# pt3MX.net
KiCad netlist of a schematic drawn in EAGLE
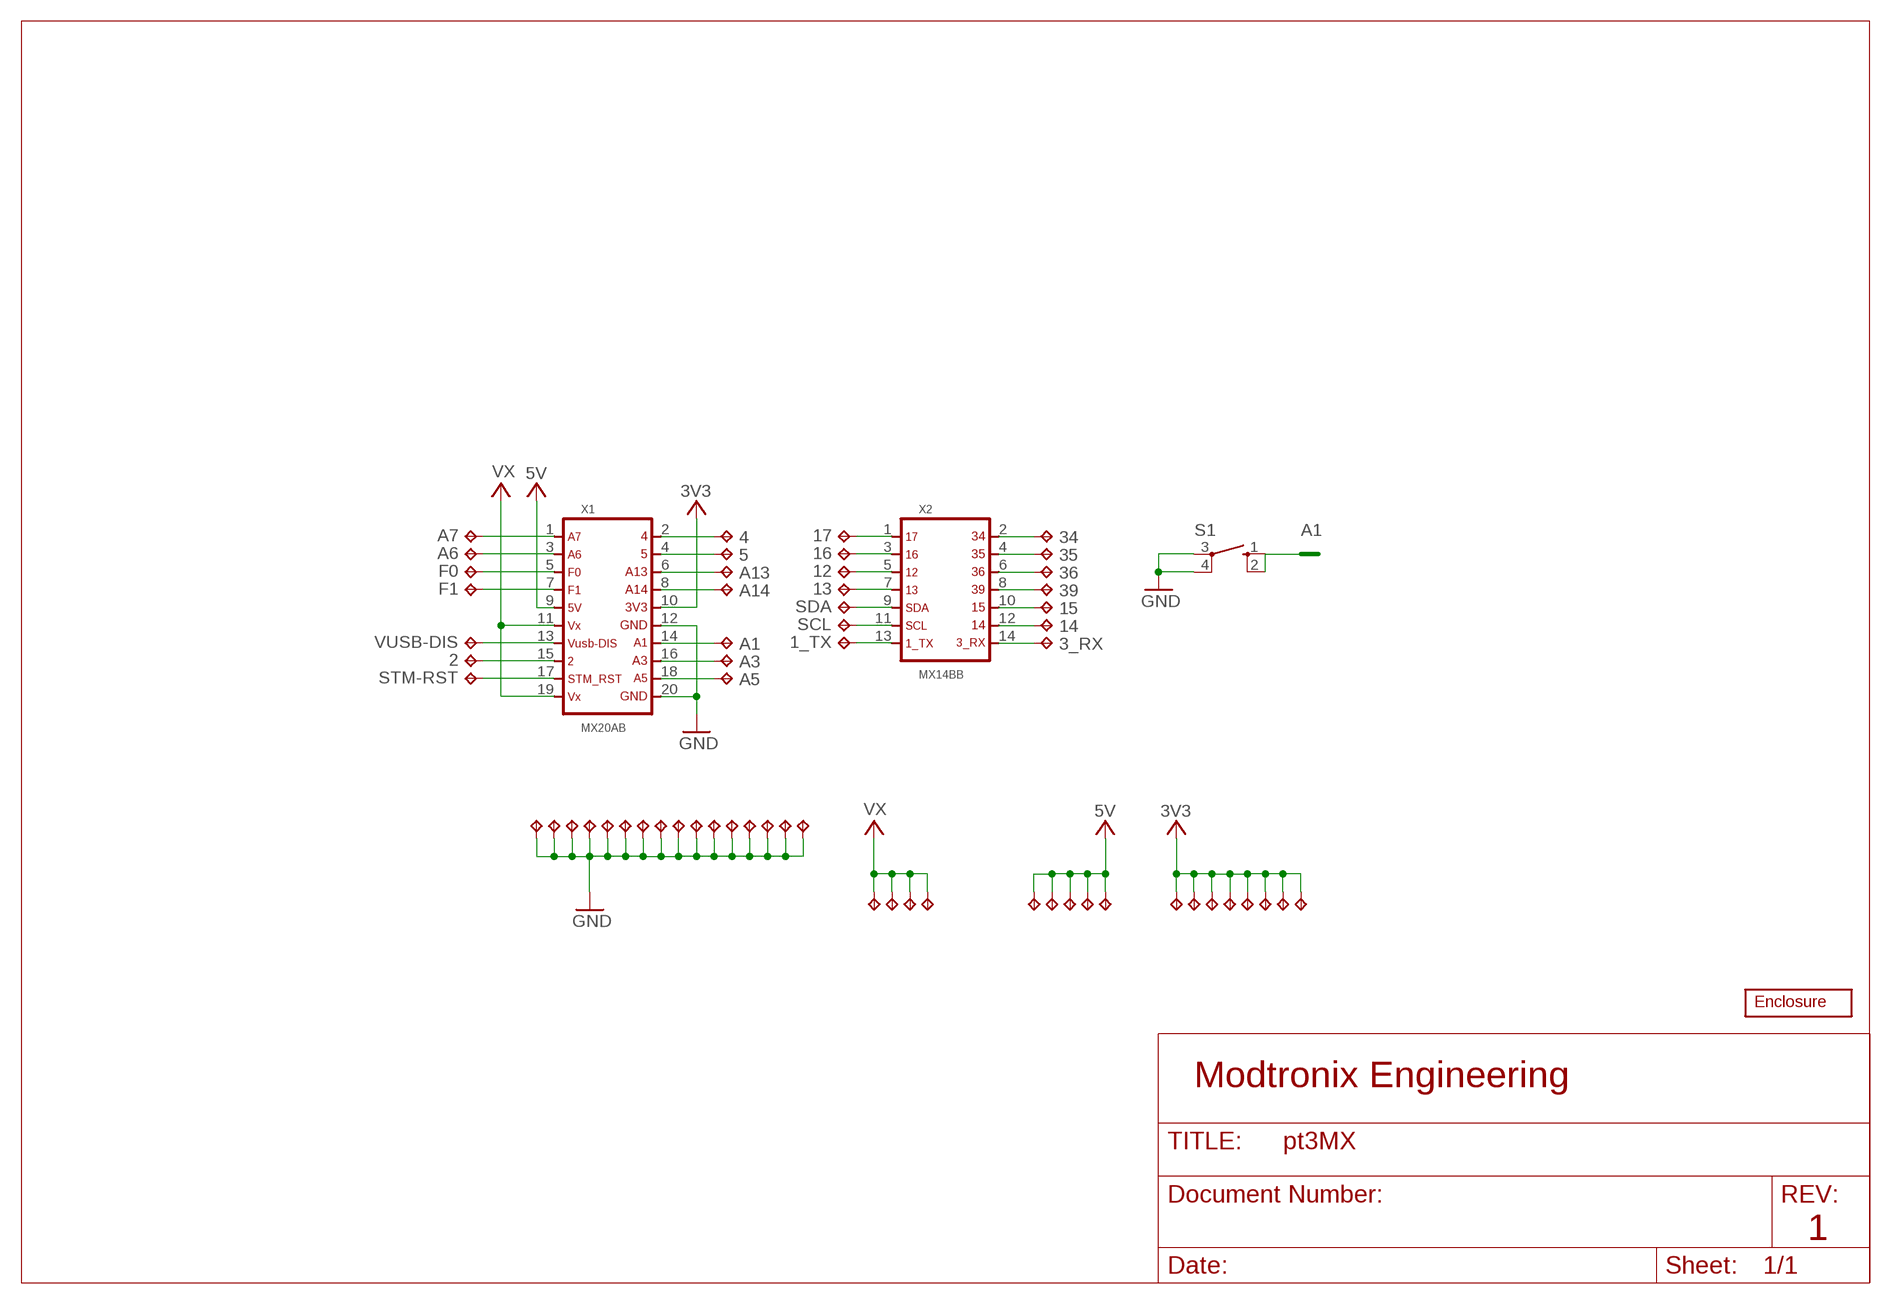
[diagram p0: schematic, sheet 1]

(export (version "E")
  (design (tool "Eeschema 10.0.6"))
  (components
    (comp (ref "1_TX")
      (value "TPD10B")
      (footprint "eagle-import:TP-10B")
      (libsource (lib "eagle-import") (part "TPD10B"))
    )
    (comp (ref "2")
      (value "TPD10B")
      (footprint "eagle-import:TP-10B")
      (libsource (lib "eagle-import") (part "TPD10B"))
    )
    (comp (ref "3_RX")
      (value "TPD10B")
      (footprint "eagle-import:TP-10B")
      (libsource (lib "eagle-import") (part "TPD10B"))
    )
    (comp (ref "4")
      (value "TPD10C")
      (footprint "eagle-import:TP-10C")
      (libsource (lib "eagle-import") (part "TPD10C"))
    )
    (comp (ref "5")
      (value "TPD10B")
      (footprint "eagle-import:TP-10B")
      (libsource (lib "eagle-import") (part "TPD10B"))
    )
    (comp (ref "12")
      (value "TPD10B")
      (footprint "eagle-import:TP-10B")
      (libsource (lib "eagle-import") (part "TPD10B"))
    )
    (comp (ref "13")
      (value "TPD10B")
      (footprint "eagle-import:TP-10B")
      (libsource (lib "eagle-import") (part "TPD10B"))
    )
    (comp (ref "14")
      (value "TPD10B")
      (footprint "eagle-import:TP-10B")
      (libsource (lib "eagle-import") (part "TPD10B"))
    )
    (comp (ref "15")
      (value "TPD10C")
      (footprint "eagle-import:TP-10C")
      (libsource (lib "eagle-import") (part "TPD10C"))
    )
    (comp (ref "16")
      (value "TPD10B")
      (footprint "eagle-import:TP-10B")
      (libsource (lib "eagle-import") (part "TPD10B"))
    )
    (comp (ref "17")
      (value "TPD10B")
      (footprint "eagle-import:TP-10B")
      (libsource (lib "eagle-import") (part "TPD10B"))
    )
    (comp (ref "34")
      (value "TPD10C")
      (footprint "eagle-import:TP-10C")
      (libsource (lib "eagle-import") (part "TPD10C"))
    )
    (comp (ref "35")
      (value "TPD10C")
      (footprint "eagle-import:TP-10C")
      (libsource (lib "eagle-import") (part "TPD10C"))
    )
    (comp (ref "36")
      (value "TPD10B")
      (footprint "eagle-import:TP-10B")
      (libsource (lib "eagle-import") (part "TPD10B"))
    )
    (comp (ref "39")
      (value "TPD10B")
      (footprint "eagle-import:TP-10B")
      (libsource (lib "eagle-import") (part "TPD10B"))
    )
    (comp (ref "A1")
      (value "TPD10-D200")
      (footprint "eagle-import:TP-10-D200")
      (libsource (lib "eagle-import") (part "TPD10-D200"))
    )
    (comp (ref "A3")
      (value "TPD10-D200")
      (footprint "eagle-import:TP-10-D200")
      (libsource (lib "eagle-import") (part "TPD10-D200"))
    )
    (comp (ref "A5")
      (value "TPD10B")
      (footprint "eagle-import:TP-10B")
      (libsource (lib "eagle-import") (part "TPD10B"))
    )
    (comp (ref "A6")
      (value "TPD10B")
      (footprint "eagle-import:TP-10B")
      (libsource (lib "eagle-import") (part "TPD10B"))
    )
    (comp (ref "A7")
      (value "TPD10B")
      (footprint "eagle-import:TP-10B")
      (libsource (lib "eagle-import") (part "TPD10B"))
    )
    (comp (ref "A13")
      (value "TPD10B")
      (footprint "eagle-import:TP-10B")
      (libsource (lib "eagle-import") (part "TPD10B"))
    )
    (comp (ref "A14")
      (value "TPD10C")
      (footprint "eagle-import:TP-10C")
      (libsource (lib "eagle-import") (part "TPD10C"))
    )
    (comp (ref "F0")
      (value "TPD10C")
      (footprint "eagle-import:TP-10C")
      (libsource (lib "eagle-import") (part "TPD10C"))
    )
    (comp (ref "F1")
      (value "TPD10-D200")
      (footprint "eagle-import:TP-10-D200")
      (libsource (lib "eagle-import") (part "TPD10-D200"))
    )
    (comp (ref "S1")
      (value "SWITCH-MICRO")
      (footprint "eagle-import:SW-TACTILE-4P-TH")
      (libsource (lib "eagle-import") (part "SWITCH-MICRO"))
    )
    (comp (ref "SCL")
      (value "TPD10B")
      (footprint "eagle-import:TP-10B")
      (libsource (lib "eagle-import") (part "TPD10B"))
    )
    (comp (ref "SDA")
      (value "TPD10C")
      (footprint "eagle-import:TP-10C")
      (libsource (lib "eagle-import") (part "TPD10C"))
    )
    (comp (ref "STM-RST")
      (value "TPD10B")
      (footprint "eagle-import:TP-10B")
      (libsource (lib "eagle-import") (part "TPD10B"))
    )
    (comp (ref "U$1")
      (value "ENC_2015SMX-AND-EC-B")
      (footprint "eagle-import:ENC_2015S_3H_MX-AND-EC_DIM-MSR_B")
      (libsource (lib "eagle-import") (part "ENC_2015SMX-AND-EC-B"))
    )
    (comp (ref "U$2")
      (value "TPD10-D205")
      (footprint "eagle-import:TP-10-D205")
      (libsource (lib "eagle-import") (part "TPD10-D205"))
    )
    (comp (ref "U$5")
      (value "TPD10D")
      (footprint "eagle-import:TP-10D")
      (libsource (lib "eagle-import") (part "TPD10D"))
    )
    (comp (ref "U$6")
      (value "TPD10-D205")
      (footprint "eagle-import:TP-10-D205")
      (libsource (lib "eagle-import") (part "TPD10-D205"))
    )
    (comp (ref "U$7")
      (value "TPD10-D205")
      (footprint "eagle-import:TP-10-D205")
      (libsource (lib "eagle-import") (part "TPD10-D205"))
    )
    (comp (ref "U$8")
      (value "TPD10-D205")
      (footprint "eagle-import:TP-10-D205")
      (libsource (lib "eagle-import") (part "TPD10-D205"))
    )
    (comp (ref "U$10")
      (value "TPD10D")
      (footprint "eagle-import:TP-10D")
      (libsource (lib "eagle-import") (part "TPD10D"))
    )
    (comp (ref "U$11")
      (value "TPD10C")
      (footprint "eagle-import:TP-10C")
      (libsource (lib "eagle-import") (part "TPD10C"))
    )
    (comp (ref "U$12")
      (value "TPD10-D205")
      (footprint "eagle-import:TP-10-D205")
      (libsource (lib "eagle-import") (part "TPD10-D205"))
    )
    (comp (ref "U$13")
      (value "TPD10C")
      (footprint "eagle-import:TP-10C")
      (libsource (lib "eagle-import") (part "TPD10C"))
    )
    (comp (ref "U$14")
      (value "TPD10")
      (footprint "eagle-import:TP-10")
      (libsource (lib "eagle-import") (part "TPD10"))
    )
    (comp (ref "U$17")
      (value "TPD10-D205")
      (footprint "eagle-import:TP-10-D205")
      (libsource (lib "eagle-import") (part "TPD10-D205"))
    )
    (comp (ref "U$22")
      (value "TPD10-D205")
      (footprint "eagle-import:TP-10-D205")
      (libsource (lib "eagle-import") (part "TPD10-D205"))
    )
    (comp (ref "U$23")
      (value "TPD10C")
      (footprint "eagle-import:TP-10C")
      (libsource (lib "eagle-import") (part "TPD10C"))
    )
    (comp (ref "U$24")
      (value "TPD10C")
      (footprint "eagle-import:TP-10C")
      (libsource (lib "eagle-import") (part "TPD10C"))
    )
    (comp (ref "U$25")
      (value "TPD10C")
      (footprint "eagle-import:TP-10C")
      (libsource (lib "eagle-import") (part "TPD10C"))
    )
    (comp (ref "U$26")
      (value "TPD10C")
      (footprint "eagle-import:TP-10C")
      (libsource (lib "eagle-import") (part "TPD10C"))
    )
    (comp (ref "U$27")
      (value "TPD10C")
      (footprint "eagle-import:TP-10C")
      (libsource (lib "eagle-import") (part "TPD10C"))
    )
    (comp (ref "U$28")
      (value "TPD10C")
      (footprint "eagle-import:TP-10C")
      (libsource (lib "eagle-import") (part "TPD10C"))
    )
    (comp (ref "U$29")
      (value "TPD10C")
      (footprint "eagle-import:TP-10C")
      (libsource (lib "eagle-import") (part "TPD10C"))
    )
    (comp (ref "U$30")
      (value "TPD10C")
      (footprint "eagle-import:TP-10C")
      (libsource (lib "eagle-import") (part "TPD10C"))
    )
    (comp (ref "U$31")
      (value "TPD10C")
      (footprint "eagle-import:TP-10C")
      (libsource (lib "eagle-import") (part "TPD10C"))
    )
    (comp (ref "U$32")
      (value "TPD10C")
      (footprint "eagle-import:TP-10C")
      (libsource (lib "eagle-import") (part "TPD10C"))
    )
    (comp (ref "U$33")
      (value "TPD10B")
      (footprint "eagle-import:TP-10B")
      (libsource (lib "eagle-import") (part "TPD10B"))
    )
    (comp (ref "U$34")
      (value "TPD10C")
      (footprint "eagle-import:TP-10C")
      (libsource (lib "eagle-import") (part "TPD10C"))
    )
    (comp (ref "U$35")
      (value "TPD10C")
      (footprint "eagle-import:TP-10C")
      (libsource (lib "eagle-import") (part "TPD10C"))
    )
    (comp (ref "U$36")
      (value "TPD10C")
      (footprint "eagle-import:TP-10C")
      (libsource (lib "eagle-import") (part "TPD10C"))
    )
    (comp (ref "U$53")
      (value "TPD10-D205")
      (footprint "eagle-import:TP-10-D205")
      (libsource (lib "eagle-import") (part "TPD10-D205"))
    )
    (comp (ref "U$58")
      (value "TPD10C")
      (footprint "eagle-import:TP-10C")
      (libsource (lib "eagle-import") (part "TPD10C"))
    )
    (comp (ref "U$60")
      (value "TPD10-D205")
      (footprint "eagle-import:TP-10-D205")
      (libsource (lib "eagle-import") (part "TPD10-D205"))
    )
    (comp (ref "U$85")
      (value "TPD10-D205")
      (footprint "eagle-import:TP-10-D205")
      (libsource (lib "eagle-import") (part "TPD10-D205"))
    )
    (comp (ref "U$86")
      (value "TPD10-D205")
      (footprint "eagle-import:TP-10-D205")
      (libsource (lib "eagle-import") (part "TPD10-D205"))
    )
    (comp (ref "U$87")
      (value "TPD10-D205")
      (footprint "eagle-import:TP-10-D205")
      (libsource (lib "eagle-import") (part "TPD10-D205"))
    )
    (comp (ref "U$90")
      (value "TPD10-D205")
      (footprint "eagle-import:TP-10-D205")
      (libsource (lib "eagle-import") (part "TPD10-D205"))
    )
    (comp (ref "VUSB-DIS")
      (value "TPD10B")
      (footprint "eagle-import:TP-10B")
      (libsource (lib "eagle-import") (part "TPD10B"))
    )
    (comp (ref "X1")
      (value "MX20AB")
      (footprint "eagle-import:MA10-2-NONUM")
      (libsource (lib "eagle-import") (part "MX20AB"))
    )
    (comp (ref "X2")
      (value "MX14BB")
      (footprint "eagle-import:MA07-2-NONUM")
      (libsource (lib "eagle-import") (part "MX14BB"))
    )
  )
  (nets
    (net (code "1") (name "/A1") (class "Default")
      (node (ref "A1") (pin "1") (pinfunction "TP_1") (pintype "input"))
      (node (ref "S1") (pin "1") (pinfunction "S_1") (pintype "passive"))
      (node (ref "S1") (pin "2") (pinfunction "S1_2") (pintype "passive"))
      (node (ref "X1") (pin "14") (pinfunction "14_14") (pintype "passive"))
    )
    (net (code "2") (name "3V3") (class "Default")
      (node (ref "U$14") (pin "1") (pinfunction "TP_1") (pintype "input"))
      (node (ref "U$25") (pin "1") (pinfunction "TP_1") (pintype "input"))
      (node (ref "U$26") (pin "1") (pinfunction "TP_1") (pintype "input"))
      (node (ref "U$31") (pin "1") (pinfunction "TP_1") (pintype "input"))
      (node (ref "U$32") (pin "1") (pinfunction "TP_1") (pintype "input"))
      (node (ref "U$53") (pin "1") (pinfunction "TP_1") (pintype "input"))
      (node (ref "U$85") (pin "1") (pinfunction "TP_1") (pintype "input"))
      (node (ref "U$86") (pin "1") (pinfunction "TP_1") (pintype "input"))
      (node (ref "X1") (pin "10") (pinfunction "10_10") (pintype "passive"))
    )
    (net (code "3") (name "5V") (class "Default")
      (node (ref "U$12") (pin "1") (pinfunction "TP_1") (pintype "input"))
      (node (ref "U$13") (pin "1") (pinfunction "TP_1") (pintype "input"))
      (node (ref "U$23") (pin "1") (pinfunction "TP_1") (pintype "input"))
      (node (ref "U$24") (pin "1") (pinfunction "TP_1") (pintype "input"))
      (node (ref "U$87") (pin "1") (pinfunction "TP_1") (pintype "input"))
      (node (ref "X1") (pin "9") (pinfunction "9_9") (pintype "passive"))
    )
    (net (code "4") (name "GND") (class "Default")
      (node (ref "S1") (pin "3") (pinfunction "P_3") (pintype "passive"))
      (node (ref "S1") (pin "4") (pinfunction "P1_4") (pintype "passive"))
      (node (ref "U$10") (pin "1") (pinfunction "TP_1") (pintype "input"))
      (node (ref "U$11") (pin "1") (pinfunction "TP_1") (pintype "input"))
      (node (ref "U$17") (pin "1") (pinfunction "TP_1") (pintype "input"))
      (node (ref "U$22") (pin "1") (pinfunction "TP_1") (pintype "input"))
      (node (ref "U$27") (pin "1") (pinfunction "TP_1") (pintype "input"))
      (node (ref "U$28") (pin "1") (pinfunction "TP_1") (pintype "input"))
      (node (ref "U$29") (pin "1") (pinfunction "TP_1") (pintype "input"))
      (node (ref "U$30") (pin "1") (pinfunction "TP_1") (pintype "input"))
      (node (ref "U$34") (pin "1") (pinfunction "TP_1") (pintype "input"))
      (node (ref "U$35") (pin "1") (pinfunction "TP_1") (pintype "input"))
      (node (ref "U$36") (pin "1") (pinfunction "TP_1") (pintype "input"))
      (node (ref "U$5") (pin "1") (pinfunction "TP_1") (pintype "input"))
      (node (ref "U$6") (pin "1") (pinfunction "TP_1") (pintype "input"))
      (node (ref "U$60") (pin "1") (pinfunction "TP_1") (pintype "input"))
      (node (ref "U$7") (pin "1") (pinfunction "TP_1") (pintype "input"))
      (node (ref "U$8") (pin "1") (pinfunction "TP_1") (pintype "input"))
      (node (ref "X1") (pin "12") (pinfunction "12_12") (pintype "passive"))
      (node (ref "X1") (pin "20") (pinfunction "20_20") (pintype "passive"))
    )
    (net (code "5") (name "Net-(1_TX-TP)") (class "Default")
      (node (ref "1_TX") (pin "1") (pinfunction "TP_1") (pintype "input"))
      (node (ref "X2") (pin "13") (pinfunction "13_13") (pintype "passive"))
    )
    (net (code "6") (name "Net-(2-TP)") (class "Default")
      (node (ref "2") (pin "1") (pinfunction "TP_1") (pintype "input"))
      (node (ref "X1") (pin "15") (pinfunction "15_15") (pintype "passive"))
    )
    (net (code "7") (name "Net-(3_RX-TP)") (class "Default")
      (node (ref "3_RX") (pin "1") (pinfunction "TP_1") (pintype "input"))
      (node (ref "X2") (pin "14") (pinfunction "14_14") (pintype "passive"))
    )
    (net (code "8") (name "Net-(4-TP)") (class "Default")
      (node (ref "4") (pin "1") (pinfunction "TP_1") (pintype "input"))
      (node (ref "X1") (pin "2") (pinfunction "2_2") (pintype "passive"))
    )
    (net (code "9") (name "Net-(5-TP)") (class "Default")
      (node (ref "5") (pin "1") (pinfunction "TP_1") (pintype "input"))
      (node (ref "X1") (pin "4") (pinfunction "4_4") (pintype "passive"))
    )
    (net (code "10") (name "Net-(12-TP)") (class "Default")
      (node (ref "12") (pin "1") (pinfunction "TP_1") (pintype "input"))
      (node (ref "X2") (pin "5") (pinfunction "5_5") (pintype "passive"))
    )
    (net (code "11") (name "Net-(13-TP)") (class "Default")
      (node (ref "13") (pin "1") (pinfunction "TP_1") (pintype "input"))
      (node (ref "X2") (pin "7") (pinfunction "7_7") (pintype "passive"))
    )
    (net (code "12") (name "Net-(14-TP)") (class "Default")
      (node (ref "14") (pin "1") (pinfunction "TP_1") (pintype "input"))
      (node (ref "X2") (pin "12") (pinfunction "12_12") (pintype "passive"))
    )
    (net (code "13") (name "Net-(15-TP)") (class "Default")
      (node (ref "15") (pin "1") (pinfunction "TP_1") (pintype "input"))
      (node (ref "X2") (pin "10") (pinfunction "10_10") (pintype "passive"))
    )
    (net (code "14") (name "Net-(16-TP)") (class "Default")
      (node (ref "16") (pin "1") (pinfunction "TP_1") (pintype "input"))
      (node (ref "X2") (pin "3") (pinfunction "3_3") (pintype "passive"))
    )
    (net (code "15") (name "Net-(17-TP)") (class "Default")
      (node (ref "17") (pin "1") (pinfunction "TP_1") (pintype "input"))
      (node (ref "X2") (pin "1") (pinfunction "1_1") (pintype "passive"))
    )
    (net (code "16") (name "Net-(34-TP)") (class "Default")
      (node (ref "34") (pin "1") (pinfunction "TP_1") (pintype "input"))
      (node (ref "X2") (pin "2") (pinfunction "2_2") (pintype "passive"))
    )
    (net (code "17") (name "Net-(35-TP)") (class "Default")
      (node (ref "35") (pin "1") (pinfunction "TP_1") (pintype "input"))
      (node (ref "X2") (pin "4") (pinfunction "4_4") (pintype "passive"))
    )
    (net (code "18") (name "Net-(36-TP)") (class "Default")
      (node (ref "36") (pin "1") (pinfunction "TP_1") (pintype "input"))
      (node (ref "X2") (pin "6") (pinfunction "6_6") (pintype "passive"))
    )
    (net (code "19") (name "Net-(39-TP)") (class "Default")
      (node (ref "39") (pin "1") (pinfunction "TP_1") (pintype "input"))
      (node (ref "X2") (pin "8") (pinfunction "8_8") (pintype "passive"))
    )
    (net (code "20") (name "Net-(A3-TP)") (class "Default")
      (node (ref "A3") (pin "1") (pinfunction "TP_1") (pintype "input"))
      (node (ref "X1") (pin "16") (pinfunction "16_16") (pintype "passive"))
    )
    (net (code "21") (name "Net-(A5-TP)") (class "Default")
      (node (ref "A5") (pin "1") (pinfunction "TP_1") (pintype "input"))
      (node (ref "X1") (pin "18") (pinfunction "18_18") (pintype "passive"))
    )
    (net (code "22") (name "Net-(A6-TP)") (class "Default")
      (node (ref "A6") (pin "1") (pinfunction "TP_1") (pintype "input"))
      (node (ref "X1") (pin "3") (pinfunction "3_3") (pintype "passive"))
    )
    (net (code "23") (name "Net-(A7-TP)") (class "Default")
      (node (ref "A7") (pin "1") (pinfunction "TP_1") (pintype "input"))
      (node (ref "X1") (pin "1") (pinfunction "1_1") (pintype "passive"))
    )
    (net (code "24") (name "Net-(A13-TP)") (class "Default")
      (node (ref "A13") (pin "1") (pinfunction "TP_1") (pintype "input"))
      (node (ref "X1") (pin "6") (pinfunction "6_6") (pintype "passive"))
    )
    (net (code "25") (name "Net-(A14-TP)") (class "Default")
      (node (ref "A14") (pin "1") (pinfunction "TP_1") (pintype "input"))
      (node (ref "X1") (pin "8") (pinfunction "8_8") (pintype "passive"))
    )
    (net (code "26") (name "Net-(F0-TP)") (class "Default")
      (node (ref "F0") (pin "1") (pinfunction "TP_1") (pintype "input"))
      (node (ref "X1") (pin "5") (pinfunction "5_5") (pintype "passive"))
    )
    (net (code "27") (name "Net-(F1-TP)") (class "Default")
      (node (ref "F1") (pin "1") (pinfunction "TP_1") (pintype "input"))
      (node (ref "X1") (pin "7") (pinfunction "7_7") (pintype "passive"))
    )
    (net (code "28") (name "Net-(SCL-TP)") (class "Default")
      (node (ref "SCL") (pin "1") (pinfunction "TP_1") (pintype "input"))
      (node (ref "X2") (pin "11") (pinfunction "11_11") (pintype "passive"))
    )
    (net (code "29") (name "Net-(SDA-TP)") (class "Default")
      (node (ref "SDA") (pin "1") (pinfunction "TP_1") (pintype "input"))
      (node (ref "X2") (pin "9") (pinfunction "9_9") (pintype "passive"))
    )
    (net (code "30") (name "Net-(STM-RST-TP)") (class "Default")
      (node (ref "STM-RST") (pin "1") (pinfunction "TP_1") (pintype "input"))
      (node (ref "X1") (pin "17") (pinfunction "17_17") (pintype "passive"))
    )
    (net (code "31") (name "Net-(VUSB-DIS-TP)") (class "Default")
      (node (ref "VUSB-DIS") (pin "1") (pinfunction "TP_1") (pintype "input"))
      (node (ref "X1") (pin "13") (pinfunction "13_13") (pintype "passive"))
    )
    (net (code "32") (name "VX") (class "Default")
      (node (ref "U$2") (pin "1") (pinfunction "TP_1") (pintype "input"))
      (node (ref "U$33") (pin "1") (pinfunction "TP_1") (pintype "input"))
      (node (ref "U$58") (pin "1") (pinfunction "TP_1") (pintype "input"))
      (node (ref "U$90") (pin "1") (pinfunction "TP_1") (pintype "input"))
      (node (ref "X1") (pin "11") (pinfunction "11_11") (pintype "passive"))
      (node (ref "X1") (pin "19") (pinfunction "19_19") (pintype "passive"))
    )
  )
)
